# ANALOG_IO.net
KiCad netlist of a schematic drawn in Altium Designer
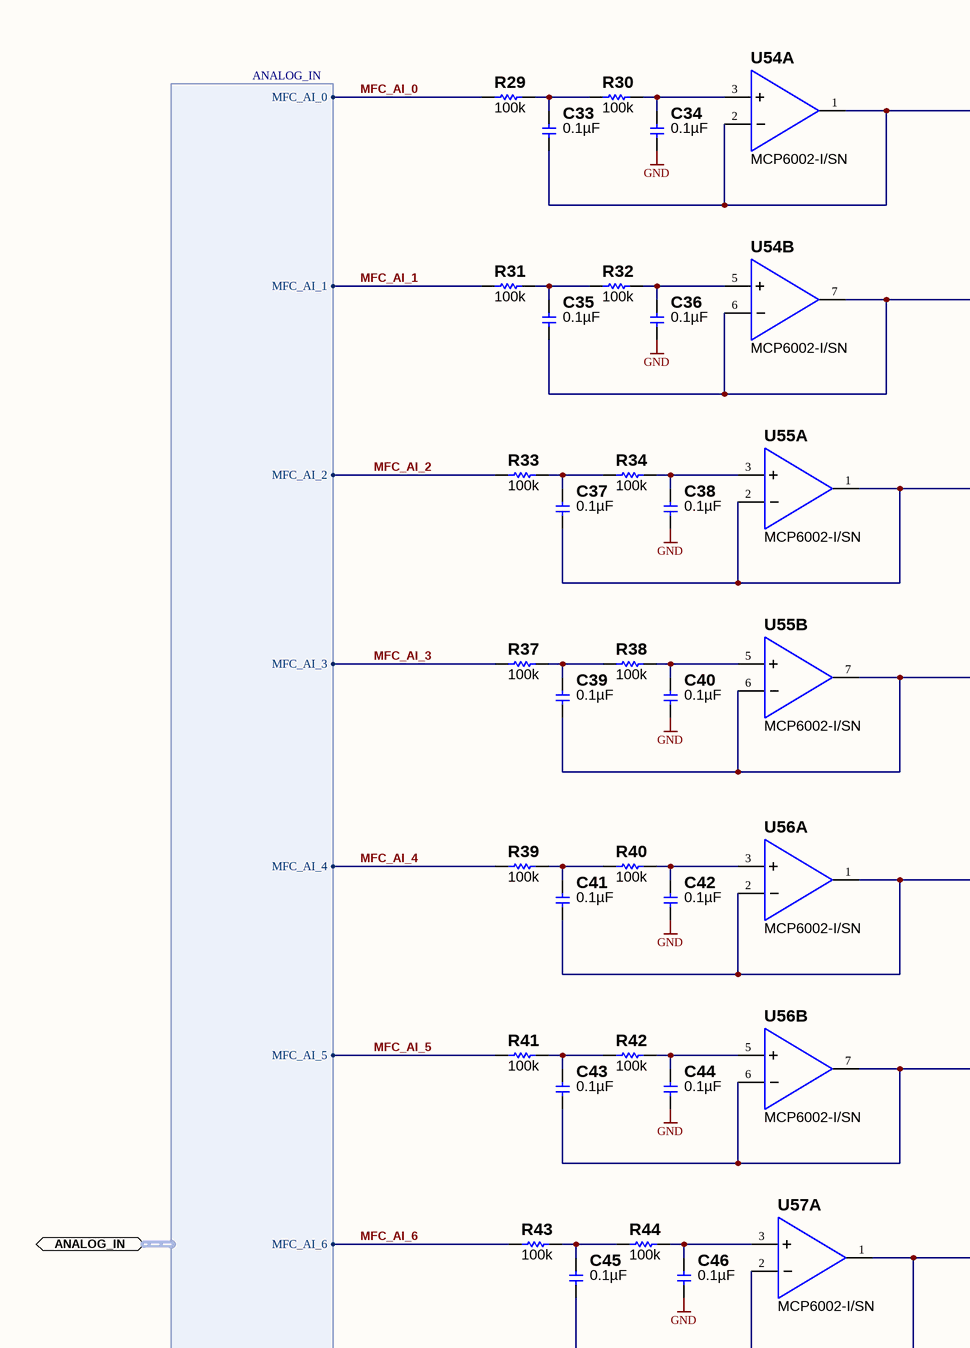
[diagram p0: ANALOG_IO.SchDoc, top left]
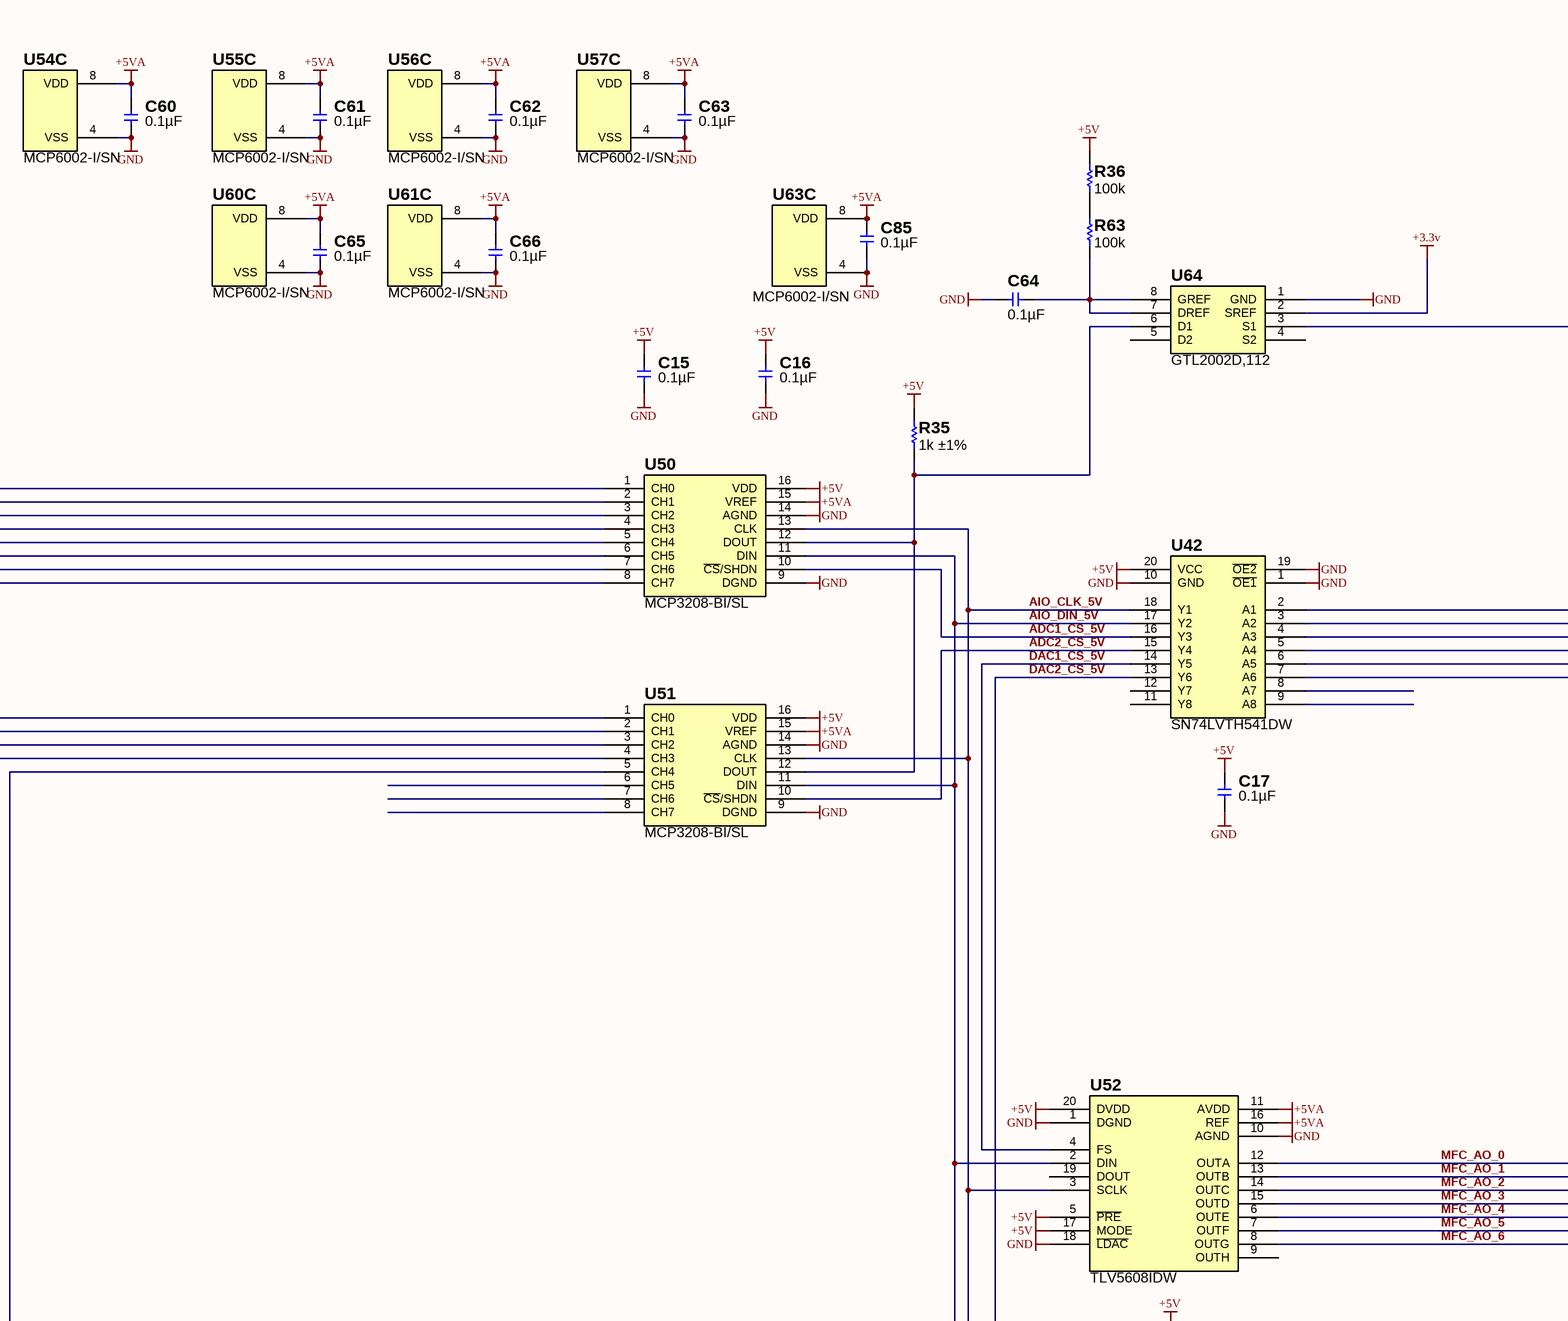
[diagram p1: ANALOG_IO.SchDoc, top middle]
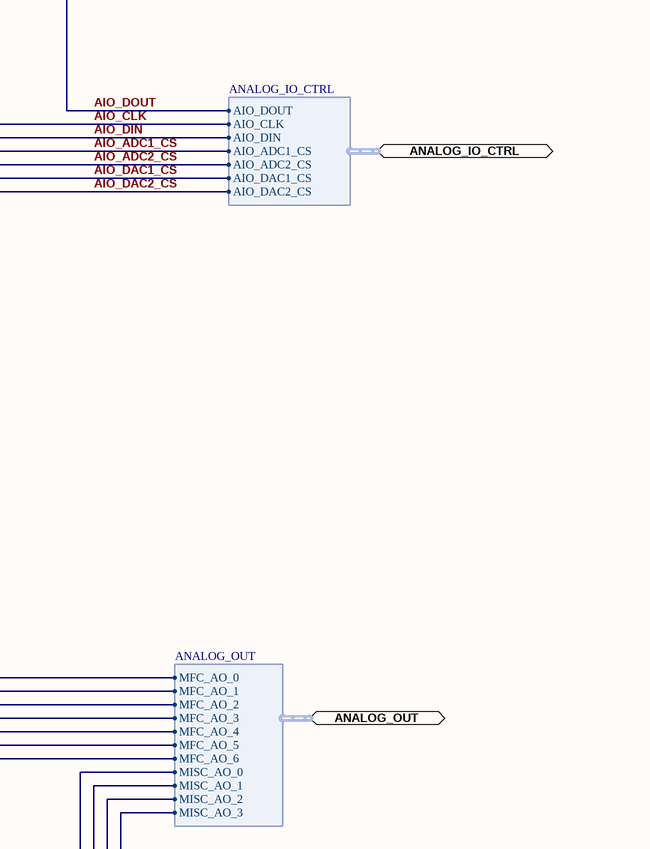
[diagram p2: ANALOG_IO.SchDoc, top right]
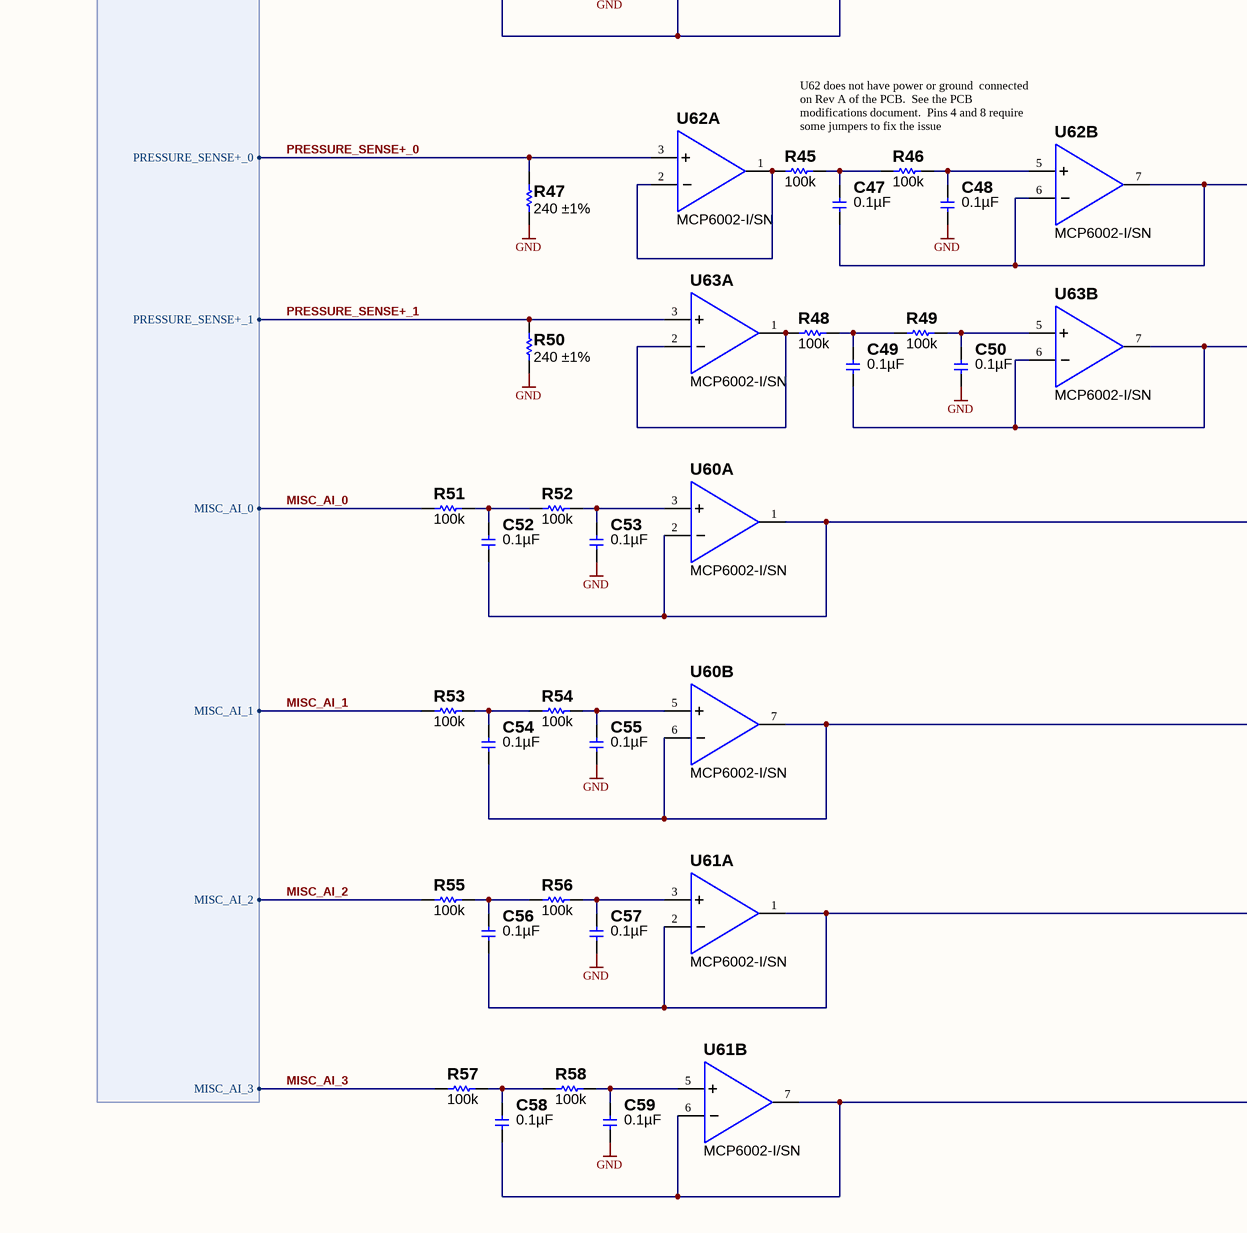
[diagram p3: ANALOG_IO.SchDoc, bottom left]
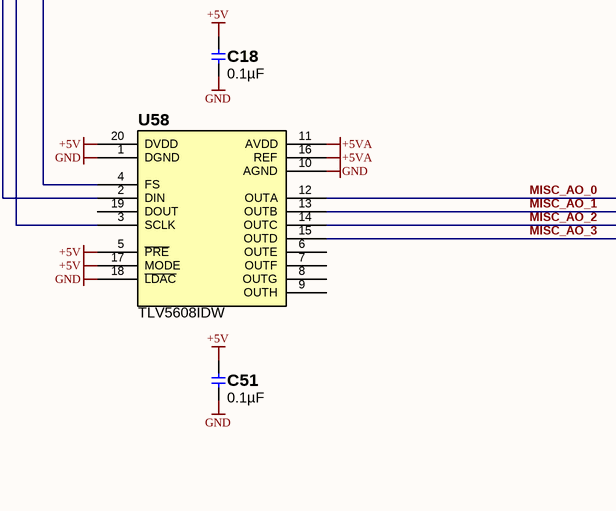
[diagram p4: ANALOG_IO.SchDoc, bottom middle]
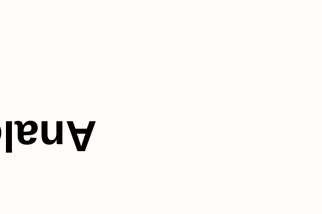
[diagram p5: ANALOG_IO.SchDoc, bottom right]

(export (version "E")
  (design (tool "Eeschema 10.0.6"))
  (components
    (comp (ref "C15")
      (value "0.1µF")
      (footprint "C0805_LD")
      (description "CAP CER 0.1UF 50V 10% X7R 0805")
      (fields
        (field (name "MANUFACTURER PART NUMBER") "GRM21BR71H104KA01L")
        (field (name "MANUFACTURER") "Murata Electronics North America")
      )
      (libsource (lib "Capacitors") (part "C_2P_NP"))
    )
    (comp (ref "C16")
      (value "0.1µF")
      (footprint "C0805_LD")
      (description "CAP CER 0.1UF 50V 10% X7R 0805")
      (fields
        (field (name "MANUFACTURER PART NUMBER") "GRM21BR71H104KA01L")
        (field (name "MANUFACTURER") "Murata Electronics North America")
      )
      (libsource (lib "Capacitors") (part "C_2P_NP"))
    )
    (comp (ref "C17")
      (value "0.1µF")
      (footprint "C0805_LD")
      (description "CAP CER 0.1UF 50V 10% X7R 0805")
      (fields
        (field (name "MANUFACTURER PART NUMBER") "GRM21BR71H104KA01L")
        (field (name "MANUFACTURER") "Murata Electronics North America")
      )
      (libsource (lib "Capacitors") (part "C_2P_NP"))
    )
    (comp (ref "C18")
      (value "0.1µF")
      (footprint "C0805_LD")
      (description "CAP CER 0.1UF 50V 10% X7R 0805")
      (fields
        (field (name "MANUFACTURER PART NUMBER") "GRM21BR71H104KA01L")
        (field (name "MANUFACTURER") "Murata Electronics North America")
      )
      (libsource (lib "Capacitors") (part "C_2P_NP"))
    )
    (comp (ref "C33")
      (value "0.1µF")
      (footprint "C0805_LD")
      (description "CAP CER 0.1UF 50V 10% X7R 0805")
      (fields
        (field (name "MANUFACTURER PART NUMBER") "GRM21BR71H104KA01L")
        (field (name "MANUFACTURER") "Murata Electronics North America")
      )
      (libsource (lib "Capacitors") (part "C_2P_NP"))
    )
    (comp (ref "C34")
      (value "0.1µF")
      (footprint "C0805_LD")
      (description "CAP CER 0.1UF 50V 10% X7R 0805")
      (fields
        (field (name "MANUFACTURER PART NUMBER") "GRM21BR71H104KA01L")
        (field (name "MANUFACTURER") "Murata Electronics North America")
      )
      (libsource (lib "Capacitors") (part "C_2P_NP"))
    )
    (comp (ref "C35")
      (value "0.1µF")
      (footprint "C0805_LD")
      (description "CAP CER 0.1UF 50V 10% X7R 0805")
      (fields
        (field (name "MANUFACTURER PART NUMBER") "GRM21BR71H104KA01L")
        (field (name "MANUFACTURER") "Murata Electronics North America")
      )
      (libsource (lib "Capacitors") (part "C_2P_NP"))
    )
    (comp (ref "C36")
      (value "0.1µF")
      (footprint "C0805_LD")
      (description "CAP CER 0.1UF 50V 10% X7R 0805")
      (fields
        (field (name "MANUFACTURER PART NUMBER") "GRM21BR71H104KA01L")
        (field (name "MANUFACTURER") "Murata Electronics North America")
      )
      (libsource (lib "Capacitors") (part "C_2P_NP"))
    )
    (comp (ref "C37")
      (value "0.1µF")
      (footprint "C0805_LD")
      (description "CAP CER 0.1UF 50V 10% X7R 0805")
      (fields
        (field (name "MANUFACTURER PART NUMBER") "GRM21BR71H104KA01L")
        (field (name "MANUFACTURER") "Murata Electronics North America")
      )
      (libsource (lib "Capacitors") (part "C_2P_NP"))
    )
    (comp (ref "C38")
      (value "0.1µF")
      (footprint "C0805_LD")
      (description "CAP CER 0.1UF 50V 10% X7R 0805")
      (fields
        (field (name "MANUFACTURER PART NUMBER") "GRM21BR71H104KA01L")
        (field (name "MANUFACTURER") "Murata Electronics North America")
      )
      (libsource (lib "Capacitors") (part "C_2P_NP"))
    )
    (comp (ref "C39")
      (value "0.1µF")
      (footprint "C0805_LD")
      (description "CAP CER 0.1UF 50V 10% X7R 0805")
      (fields
        (field (name "MANUFACTURER PART NUMBER") "GRM21BR71H104KA01L")
        (field (name "MANUFACTURER") "Murata Electronics North America")
      )
      (libsource (lib "Capacitors") (part "C_2P_NP"))
    )
    (comp (ref "C40")
      (value "0.1µF")
      (footprint "C0805_LD")
      (description "CAP CER 0.1UF 50V 10% X7R 0805")
      (fields
        (field (name "MANUFACTURER PART NUMBER") "GRM21BR71H104KA01L")
        (field (name "MANUFACTURER") "Murata Electronics North America")
      )
      (libsource (lib "Capacitors") (part "C_2P_NP"))
    )
    (comp (ref "C41")
      (value "0.1µF")
      (footprint "C0805_LD")
      (description "CAP CER 0.1UF 50V 10% X7R 0805")
      (fields
        (field (name "MANUFACTURER PART NUMBER") "GRM21BR71H104KA01L")
        (field (name "MANUFACTURER") "Murata Electronics North America")
      )
      (libsource (lib "Capacitors") (part "C_2P_NP"))
    )
    (comp (ref "C42")
      (value "0.1µF")
      (footprint "C0805_LD")
      (description "CAP CER 0.1UF 50V 10% X7R 0805")
      (fields
        (field (name "MANUFACTURER PART NUMBER") "GRM21BR71H104KA01L")
        (field (name "MANUFACTURER") "Murata Electronics North America")
      )
      (libsource (lib "Capacitors") (part "C_2P_NP"))
    )
    (comp (ref "C43")
      (value "0.1µF")
      (footprint "C0805_LD")
      (description "CAP CER 0.1UF 50V 10% X7R 0805")
      (fields
        (field (name "MANUFACTURER PART NUMBER") "GRM21BR71H104KA01L")
        (field (name "MANUFACTURER") "Murata Electronics North America")
      )
      (libsource (lib "Capacitors") (part "C_2P_NP"))
    )
    (comp (ref "C44")
      (value "0.1µF")
      (footprint "C0805_LD")
      (description "CAP CER 0.1UF 50V 10% X7R 0805")
      (fields
        (field (name "MANUFACTURER PART NUMBER") "GRM21BR71H104KA01L")
        (field (name "MANUFACTURER") "Murata Electronics North America")
      )
      (libsource (lib "Capacitors") (part "C_2P_NP"))
    )
    (comp (ref "C45")
      (value "0.1µF")
      (footprint "C0805_LD")
      (description "CAP CER 0.1UF 50V 10% X7R 0805")
      (fields
        (field (name "MANUFACTURER PART NUMBER") "GRM21BR71H104KA01L")
        (field (name "MANUFACTURER") "Murata Electronics North America")
      )
      (libsource (lib "Capacitors") (part "C_2P_NP"))
    )
    (comp (ref "C46")
      (value "0.1µF")
      (footprint "C0805_LD")
      (description "CAP CER 0.1UF 50V 10% X7R 0805")
      (fields
        (field (name "MANUFACTURER PART NUMBER") "GRM21BR71H104KA01L")
        (field (name "MANUFACTURER") "Murata Electronics North America")
      )
      (libsource (lib "Capacitors") (part "C_2P_NP"))
    )
    (comp (ref "C47")
      (value "0.1µF")
      (footprint "C0805_LD")
      (description "CAP CER 0.1UF 50V 10% X7R 0805")
      (fields
        (field (name "MANUFACTURER PART NUMBER") "GRM21BR71H104KA01L")
        (field (name "MANUFACTURER") "Murata Electronics North America")
      )
      (libsource (lib "Capacitors") (part "C_2P_NP"))
    )
    (comp (ref "C48")
      (value "0.1µF")
      (footprint "C0805_LD")
      (description "CAP CER 0.1UF 50V 10% X7R 0805")
      (fields
        (field (name "MANUFACTURER PART NUMBER") "GRM21BR71H104KA01L")
        (field (name "MANUFACTURER") "Murata Electronics North America")
      )
      (libsource (lib "Capacitors") (part "C_2P_NP"))
    )
    (comp (ref "C49")
      (value "0.1µF")
      (footprint "C0805_LD")
      (description "CAP CER 0.1UF 50V 10% X7R 0805")
      (fields
        (field (name "MANUFACTURER PART NUMBER") "GRM21BR71H104KA01L")
        (field (name "MANUFACTURER") "Murata Electronics North America")
      )
      (libsource (lib "Capacitors") (part "C_2P_NP"))
    )
    (comp (ref "C50")
      (value "0.1µF")
      (footprint "C0805_LD")
      (description "CAP CER 0.1UF 50V 10% X7R 0805")
      (fields
        (field (name "MANUFACTURER PART NUMBER") "GRM21BR71H104KA01L")
        (field (name "MANUFACTURER") "Murata Electronics North America")
      )
      (libsource (lib "Capacitors") (part "C_2P_NP"))
    )
    (comp (ref "C51")
      (value "0.1µF")
      (footprint "C0805_LD")
      (description "CAP CER 0.1UF 50V 10% X7R 0805")
      (fields
        (field (name "MANUFACTURER PART NUMBER") "GRM21BR71H104KA01L")
        (field (name "MANUFACTURER") "Murata Electronics North America")
      )
      (libsource (lib "Capacitors") (part "C_2P_NP"))
    )
    (comp (ref "C52")
      (value "0.1µF")
      (footprint "C0805_LD")
      (description "CAP CER 0.1UF 50V 10% X7R 0805")
      (fields
        (field (name "MANUFACTURER PART NUMBER") "GRM21BR71H104KA01L")
        (field (name "MANUFACTURER") "Murata Electronics North America")
      )
      (libsource (lib "Capacitors") (part "C_2P_NP"))
    )
    (comp (ref "C53")
      (value "0.1µF")
      (footprint "C0805_LD")
      (description "CAP CER 0.1UF 50V 10% X7R 0805")
      (fields
        (field (name "MANUFACTURER PART NUMBER") "GRM21BR71H104KA01L")
        (field (name "MANUFACTURER") "Murata Electronics North America")
      )
      (libsource (lib "Capacitors") (part "C_2P_NP"))
    )
    (comp (ref "C54")
      (value "0.1µF")
      (footprint "C0805_LD")
      (description "CAP CER 0.1UF 50V 10% X7R 0805")
      (fields
        (field (name "MANUFACTURER PART NUMBER") "GRM21BR71H104KA01L")
        (field (name "MANUFACTURER") "Murata Electronics North America")
      )
      (libsource (lib "Capacitors") (part "C_2P_NP"))
    )
    (comp (ref "C55")
      (value "0.1µF")
      (footprint "C0805_LD")
      (description "CAP CER 0.1UF 50V 10% X7R 0805")
      (fields
        (field (name "MANUFACTURER PART NUMBER") "GRM21BR71H104KA01L")
        (field (name "MANUFACTURER") "Murata Electronics North America")
      )
      (libsource (lib "Capacitors") (part "C_2P_NP"))
    )
    (comp (ref "C56")
      (value "0.1µF")
      (footprint "C0805_LD")
      (description "CAP CER 0.1UF 50V 10% X7R 0805")
      (fields
        (field (name "MANUFACTURER PART NUMBER") "GRM21BR71H104KA01L")
        (field (name "MANUFACTURER") "Murata Electronics North America")
      )
      (libsource (lib "Capacitors") (part "C_2P_NP"))
    )
    (comp (ref "C57")
      (value "0.1µF")
      (footprint "C0805_LD")
      (description "CAP CER 0.1UF 50V 10% X7R 0805")
      (fields
        (field (name "MANUFACTURER PART NUMBER") "GRM21BR71H104KA01L")
        (field (name "MANUFACTURER") "Murata Electronics North America")
      )
      (libsource (lib "Capacitors") (part "C_2P_NP"))
    )
    (comp (ref "C58")
      (value "0.1µF")
      (footprint "C0805_LD")
      (description "CAP CER 0.1UF 50V 10% X7R 0805")
      (fields
        (field (name "MANUFACTURER PART NUMBER") "GRM21BR71H104KA01L")
        (field (name "MANUFACTURER") "Murata Electronics North America")
      )
      (libsource (lib "Capacitors") (part "C_2P_NP"))
    )
    (comp (ref "C59")
      (value "0.1µF")
      (footprint "C0805_LD")
      (description "CAP CER 0.1UF 50V 10% X7R 0805")
      (fields
        (field (name "MANUFACTURER PART NUMBER") "GRM21BR71H104KA01L")
        (field (name "MANUFACTURER") "Murata Electronics North America")
      )
      (libsource (lib "Capacitors") (part "C_2P_NP"))
    )
    (comp (ref "C60")
      (value "0.1µF")
      (footprint "C0805_LD")
      (description "CAP CER 0.1UF 50V 10% X7R 0805")
      (fields
        (field (name "MANUFACTURER PART NUMBER") "GRM21BR71H104KA01L")
        (field (name "MANUFACTURER") "Murata Electronics North America")
      )
      (libsource (lib "Capacitors") (part "C_2P_NP"))
    )
    (comp (ref "C61")
      (value "0.1µF")
      (footprint "C0805_LD")
      (description "CAP CER 0.1UF 50V 10% X7R 0805")
      (fields
        (field (name "MANUFACTURER PART NUMBER") "GRM21BR71H104KA01L")
        (field (name "MANUFACTURER") "Murata Electronics North America")
      )
      (libsource (lib "Capacitors") (part "C_2P_NP"))
    )
    (comp (ref "C62")
      (value "0.1µF")
      (footprint "C0805_LD")
      (description "CAP CER 0.1UF 50V 10% X7R 0805")
      (fields
        (field (name "MANUFACTURER PART NUMBER") "GRM21BR71H104KA01L")
        (field (name "MANUFACTURER") "Murata Electronics North America")
      )
      (libsource (lib "Capacitors") (part "C_2P_NP"))
    )
    (comp (ref "C63")
      (value "0.1µF")
      (footprint "C0805_LD")
      (description "CAP CER 0.1UF 50V 10% X7R 0805")
      (fields
        (field (name "MANUFACTURER PART NUMBER") "GRM21BR71H104KA01L")
        (field (name "MANUFACTURER") "Murata Electronics North America")
      )
      (libsource (lib "Capacitors") (part "C_2P_NP"))
    )
    (comp (ref "C64")
      (value "0.1µF")
      (footprint "C0805_LD")
      (description "CAP CER 0.1UF 50V 10% X7R 0805")
      (fields
        (field (name "MANUFACTURER PART NUMBER") "GRM21BR71H104KA01L")
        (field (name "MANUFACTURER") "Murata Electronics North America")
      )
      (libsource (lib "Capacitors") (part "C_2P_NP"))
    )
    (comp (ref "C65")
      (value "0.1µF")
      (footprint "C0805_LD")
      (description "CAP CER 0.1UF 50V 10% X7R 0805")
      (fields
        (field (name "MANUFACTURER PART NUMBER") "GRM21BR71H104KA01L")
        (field (name "MANUFACTURER") "Murata Electronics North America")
      )
      (libsource (lib "Capacitors") (part "C_2P_NP"))
    )
    (comp (ref "C66")
      (value "0.1µF")
      (footprint "C0805_LD")
      (description "CAP CER 0.1UF 50V 10% X7R 0805")
      (fields
        (field (name "MANUFACTURER PART NUMBER") "GRM21BR71H104KA01L")
        (field (name "MANUFACTURER") "Murata Electronics North America")
      )
      (libsource (lib "Capacitors") (part "C_2P_NP"))
    )
    (comp (ref "C85")
      (value "0.1µF")
      (footprint "C0805_LD")
      (description "CAP CER 0.1UF 50V 10% X7R 0805")
      (fields
        (field (name "MANUFACTURER PART NUMBER") "GRM21BR71H104KA01L")
        (field (name "MANUFACTURER") "Murata Electronics North America")
      )
      (libsource (lib "Capacitors") (part "C_2P_NP"))
    )
    (comp (ref "R29")
      (value "100k")
      (footprint "R0805_LD")
      (description "RES 100K OHM 1/8W 1% 0805 SMD")
      (fields
        (field (name "MANUFACTURER PART NUMBER") "ERJ-6ENF1003V")
        (field (name "MANUFACTURER") "Panasonic Electronic Components")
      )
      (libsource (lib "Resistors") (part "R_2P"))
    )
    (comp (ref "R30")
      (value "100k")
      (footprint "R0805_LD")
      (description "RES 100K OHM 1/8W 1% 0805 SMD")
      (fields
        (field (name "MANUFACTURER PART NUMBER") "ERJ-6ENF1003V")
        (field (name "MANUFACTURER") "Panasonic Electronic Components")
      )
      (libsource (lib "Resistors") (part "R_2P"))
    )
    (comp (ref "R31")
      (value "100k")
      (footprint "R0805_LD")
      (description "RES 100K OHM 1/8W 1% 0805 SMD")
      (fields
        (field (name "MANUFACTURER PART NUMBER") "ERJ-6ENF1003V")
        (field (name "MANUFACTURER") "Panasonic Electronic Components")
      )
      (libsource (lib "Resistors") (part "R_2P"))
    )
    (comp (ref "R32")
      (value "100k")
      (footprint "R0805_LD")
      (description "RES 100K OHM 1/8W 1% 0805 SMD")
      (fields
        (field (name "MANUFACTURER PART NUMBER") "ERJ-6ENF1003V")
        (field (name "MANUFACTURER") "Panasonic Electronic Components")
      )
      (libsource (lib "Resistors") (part "R_2P"))
    )
    (comp (ref "R33")
      (value "100k")
      (footprint "R0805_LD")
      (description "RES 100K OHM 1/8W 1% 0805 SMD")
      (fields
        (field (name "MANUFACTURER PART NUMBER") "ERJ-6ENF1003V")
        (field (name "MANUFACTURER") "Panasonic Electronic Components")
      )
      (libsource (lib "Resistors") (part "R_2P"))
    )
    (comp (ref "R34")
      (value "100k")
      (footprint "R0805_LD")
      (description "RES 100K OHM 1/8W 1% 0805 SMD")
      (fields
        (field (name "MANUFACTURER PART NUMBER") "ERJ-6ENF1003V")
        (field (name "MANUFACTURER") "Panasonic Electronic Components")
      )
      (libsource (lib "Resistors") (part "R_2P"))
    )
    (comp (ref "R35")
      (value "1k ±1%")
      (footprint "R0805_LD")
      (description "RES 1K OHM 1/8W 1% 0805 SMD")
      (fields
        (field (name "MANUFACTURER PART NUMBER") "ERJ-6ENF1001V")
        (field (name "MANUFACTURER") "Panasonic Electronic Components")
      )
      (libsource (lib "Resistors") (part "R_2P"))
    )
    (comp (ref "R36")
      (value "100k")
      (footprint "R0805_LD")
      (description "RES 100K OHM 1/8W 1% 0805 SMD")
      (fields
        (field (name "MANUFACTURER PART NUMBER") "ERJ-6ENF1003V")
        (field (name "MANUFACTURER") "Panasonic Electronic Components")
      )
      (libsource (lib "Resistors") (part "R_2P"))
    )
    (comp (ref "R37")
      (value "100k")
      (footprint "R0805_LD")
      (description "RES 100K OHM 1/8W 1% 0805 SMD")
      (fields
        (field (name "MANUFACTURER PART NUMBER") "ERJ-6ENF1003V")
        (field (name "MANUFACTURER") "Panasonic Electronic Components")
      )
      (libsource (lib "Resistors") (part "R_2P"))
    )
    (comp (ref "R38")
      (value "100k")
      (footprint "R0805_LD")
      (description "RES 100K OHM 1/8W 1% 0805 SMD")
      (fields
        (field (name "MANUFACTURER PART NUMBER") "ERJ-6ENF1003V")
        (field (name "MANUFACTURER") "Panasonic Electronic Components")
      )
      (libsource (lib "Resistors") (part "R_2P"))
    )
    (comp (ref "R39")
      (value "100k")
      (footprint "R0805_LD")
      (description "RES 100K OHM 1/8W 1% 0805 SMD")
      (fields
        (field (name "MANUFACTURER PART NUMBER") "ERJ-6ENF1003V")
        (field (name "MANUFACTURER") "Panasonic Electronic Components")
      )
      (libsource (lib "Resistors") (part "R_2P"))
    )
    (comp (ref "R40")
      (value "100k")
      (footprint "R0805_LD")
      (description "RES 100K OHM 1/8W 1% 0805 SMD")
      (fields
        (field (name "MANUFACTURER PART NUMBER") "ERJ-6ENF1003V")
        (field (name "MANUFACTURER") "Panasonic Electronic Components")
      )
      (libsource (lib "Resistors") (part "R_2P"))
    )
    (comp (ref "R41")
      (value "100k")
      (footprint "R0805_LD")
      (description "RES 100K OHM 1/8W 1% 0805 SMD")
      (fields
        (field (name "MANUFACTURER PART NUMBER") "ERJ-6ENF1003V")
        (field (name "MANUFACTURER") "Panasonic Electronic Components")
      )
      (libsource (lib "Resistors") (part "R_2P"))
    )
    (comp (ref "R42")
      (value "100k")
      (footprint "R0805_LD")
      (description "RES 100K OHM 1/8W 1% 0805 SMD")
      (fields
        (field (name "MANUFACTURER PART NUMBER") "ERJ-6ENF1003V")
        (field (name "MANUFACTURER") "Panasonic Electronic Components")
      )
      (libsource (lib "Resistors") (part "R_2P"))
    )
    (comp (ref "R43")
      (value "100k")
      (footprint "R0805_LD")
      (description "RES 100K OHM 1/8W 1% 0805 SMD")
      (fields
        (field (name "MANUFACTURER PART NUMBER") "ERJ-6ENF1003V")
        (field (name "MANUFACTURER") "Panasonic Electronic Components")
      )
      (libsource (lib "Resistors") (part "R_2P"))
    )
    (comp (ref "R44")
      (value "100k")
      (footprint "R0805_LD")
      (description "RES 100K OHM 1/8W 1% 0805 SMD")
      (fields
        (field (name "MANUFACTURER PART NUMBER") "ERJ-6ENF1003V")
        (field (name "MANUFACTURER") "Panasonic Electronic Components")
      )
      (libsource (lib "Resistors") (part "R_2P"))
    )
    (comp (ref "R45")
      (value "100k")
      (footprint "R0805_LD")
      (description "RES 100K OHM 1/8W 1% 0805 SMD")
      (fields
        (field (name "MANUFACTURER PART NUMBER") "ERJ-6ENF1003V")
        (field (name "MANUFACTURER") "Panasonic Electronic Components")
      )
      (libsource (lib "Resistors") (part "R_2P"))
    )
    (comp (ref "R46")
      (value "100k")
      (footprint "R0805_LD")
      (description "RES 100K OHM 1/8W 1% 0805 SMD")
      (fields
        (field (name "MANUFACTURER PART NUMBER") "ERJ-6ENF1003V")
        (field (name "MANUFACTURER") "Panasonic Electronic Components")
      )
      (libsource (lib "Resistors") (part "R_2P"))
    )
    (comp (ref "R47")
      (value "240 ±1%")
      (footprint "R0805_LD")
      (description "RES 240 OHM 1/8W 1% 0805 SMD")
      (fields
        (field (name "MANUFACTURER PART NUMBER") "ERJ-6ENF2400V")
        (field (name "MANUFACTURER") "Panasonic Electronic Components")
      )
      (libsource (lib "Resistors") (part "R_2P"))
    )
    (comp (ref "R48")
      (value "100k")
      (footprint "R0805_LD")
      (description "RES 100K OHM 1/8W 1% 0805 SMD")
      (fields
        (field (name "MANUFACTURER PART NUMBER") "ERJ-6ENF1003V")
        (field (name "MANUFACTURER") "Panasonic Electronic Components")
      )
      (libsource (lib "Resistors") (part "R_2P"))
    )
    (comp (ref "R49")
      (value "100k")
      (footprint "R0805_LD")
      (description "RES 100K OHM 1/8W 1% 0805 SMD")
      (fields
        (field (name "MANUFACTURER PART NUMBER") "ERJ-6ENF1003V")
        (field (name "MANUFACTURER") "Panasonic Electronic Components")
      )
      (libsource (lib "Resistors") (part "R_2P"))
    )
    (comp (ref "R50")
      (value "240 ±1%")
      (footprint "R0805_LD")
      (description "RES 240 OHM 1/8W 1% 0805 SMD")
      (fields
        (field (name "MANUFACTURER PART NUMBER") "ERJ-6ENF2400V")
        (field (name "MANUFACTURER") "Panasonic Electronic Components")
      )
      (libsource (lib "Resistors") (part "R_2P"))
    )
    (comp (ref "R51")
      (value "100k")
      (footprint "R0805_LD")
      (description "RES 100K OHM 1/8W 1% 0805 SMD")
      (fields
        (field (name "MANUFACTURER PART NUMBER") "ERJ-6ENF1003V")
        (field (name "MANUFACTURER") "Panasonic Electronic Components")
      )
      (libsource (lib "Resistors") (part "R_2P"))
    )
    (comp (ref "R52")
      (value "100k")
      (footprint "R0805_LD")
      (description "RES 100K OHM 1/8W 1% 0805 SMD")
      (fields
        (field (name "MANUFACTURER PART NUMBER") "ERJ-6ENF1003V")
        (field (name "MANUFACTURER") "Panasonic Electronic Components")
      )
      (libsource (lib "Resistors") (part "R_2P"))
    )
    (comp (ref "R53")
      (value "100k")
      (footprint "R0805_LD")
      (description "RES 100K OHM 1/8W 1% 0805 SMD")
      (fields
        (field (name "MANUFACTURER PART NUMBER") "ERJ-6ENF1003V")
        (field (name "MANUFACTURER") "Panasonic Electronic Components")
      )
      (libsource (lib "Resistors") (part "R_2P"))
    )
    (comp (ref "R54")
      (value "100k")
      (footprint "R0805_LD")
      (description "RES 100K OHM 1/8W 1% 0805 SMD")
      (fields
        (field (name "MANUFACTURER PART NUMBER") "ERJ-6ENF1003V")
        (field (name "MANUFACTURER") "Panasonic Electronic Components")
      )
      (libsource (lib "Resistors") (part "R_2P"))
    )
    (comp (ref "R55")
      (value "100k")
      (footprint "R0805_LD")
      (description "RES 100K OHM 1/8W 1% 0805 SMD")
      (fields
        (field (name "MANUFACTURER PART NUMBER") "ERJ-6ENF1003V")
        (field (name "MANUFACTURER") "Panasonic Electronic Components")
      )
      (libsource (lib "Resistors") (part "R_2P"))
    )
    (comp (ref "R56")
      (value "100k")
      (footprint "R0805_LD")
      (description "RES 100K OHM 1/8W 1% 0805 SMD")
      (fields
        (field (name "MANUFACTURER PART NUMBER") "ERJ-6ENF1003V")
        (field (name "MANUFACTURER") "Panasonic Electronic Components")
      )
      (libsource (lib "Resistors") (part "R_2P"))
    )
    (comp (ref "R57")
      (value "100k")
      (footprint "R0805_LD")
      (description "RES 100K OHM 1/8W 1% 0805 SMD")
      (fields
        (field (name "MANUFACTURER PART NUMBER") "ERJ-6ENF1003V")
        (field (name "MANUFACTURER") "Panasonic Electronic Components")
      )
      (libsource (lib "Resistors") (part "R_2P"))
    )
    (comp (ref "R58")
      (value "100k")
      (footprint "R0805_LD")
      (description "RES 100K OHM 1/8W 1% 0805 SMD")
      (fields
        (field (name "MANUFACTURER PART NUMBER") "ERJ-6ENF1003V")
        (field (name "MANUFACTURER") "Panasonic Electronic Components")
      )
      (libsource (lib "Resistors") (part "R_2P"))
    )
    (comp (ref "R63")
      (value "100k")
      (footprint "R0805_LD")
      (description "RES 100K OHM 1/8W 1% 0805 SMD")
      (fields
        (field (name "MANUFACTURER PART NUMBER") "ERJ-6ENF1003V")
        (field (name "MANUFACTURER") "Panasonic Electronic Components")
      )
      (libsource (lib "Resistors") (part "R_2P"))
    )
    (comp (ref "U42")
      (value "SN74LVTH541DW")
      (footprint "SOIC127P1030X265-20L")
      (description "IC BUFF/DVR TRI-ST 8BIT 20SOIC")
      (fields (field (name "MANUFACTURER") "Texas Instruments"))
      (libsource (lib "eIC") (part "SN74LVTH541DW"))
    )
    (comp (ref "U50")
      (value "MCP3208-BI/SL")
      (footprint "SOIC127P600X145-16L")
      (description "IC ADC 12BIT 2.7V 8CH SPI 16SOIC")
      (fields (field (name "MANUFACTURER") "Microchip Technology"))
      (libsource (lib "eIC") (part "MCP3208-BI/SL"))
    )
    (comp (ref "U51")
      (value "MCP3208-BI/SL")
      (footprint "SOIC127P600X145-16L")
      (description "IC ADC 12BIT 2.7V 8CH SPI 16SOIC")
      (fields (field (name "MANUFACTURER") "Microchip Technology"))
      (libsource (lib "eIC") (part "MCP3208-BI/SL"))
    )
    (comp (ref "U52")
      (value "TLV5608IDW")
      (footprint "SOIC127P1030X265-20L")
      (description "IC 8 CHANNEL DAC S/O 20-SOIC")
      (fields (field (name "MANUFACTURER") "Texas Instruments"))
      (libsource (lib "eIC") (part "TLV5608IDW"))
    )
    (comp (ref "U54")
      (value "MCP6002-I/SN")
      (footprint "SOIC 8")
      (description "IC OPAMP 1.8V 1MHZ DUAL 8-SOIC")
      (fields (field (name "MANUFACTURER") "Microchip Technology"))
      (libsource (lib "eIC") (part "MCP6002-I/SN"))
    )
    (comp (ref "U55")
      (value "MCP6002-I/SN")
      (footprint "SOIC 8")
      (description "IC OPAMP 1.8V 1MHZ DUAL 8-SOIC")
      (fields (field (name "MANUFACTURER") "Microchip Technology"))
      (libsource (lib "eIC") (part "MCP6002-I/SN"))
    )
    (comp (ref "U56")
      (value "MCP6002-I/SN")
      (footprint "SOIC 8")
      (description "IC OPAMP 1.8V 1MHZ DUAL 8-SOIC")
      (fields (field (name "MANUFACTURER") "Microchip Technology"))
      (libsource (lib "eIC") (part "MCP6002-I/SN"))
    )
    (comp (ref "U57")
      (value "MCP6002-I/SN")
      (footprint "SOIC 8")
      (description "IC OPAMP 1.8V 1MHZ DUAL 8-SOIC")
      (fields (field (name "MANUFACTURER") "Microchip Technology"))
      (libsource (lib "eIC") (part "MCP6002-I/SN"))
    )
    (comp (ref "U58")
      (value "TLV5608IDW")
      (footprint "SOIC127P1030X265-20L")
      (description "IC 8 CHANNEL DAC S/O 20-SOIC")
      (fields (field (name "MANUFACTURER") "Texas Instruments"))
      (libsource (lib "eIC") (part "TLV5608IDW"))
    )
    (comp (ref "U60")
      (value "MCP6002-I/SN")
      (footprint "SOIC 8")
      (description "IC OPAMP 1.8V 1MHZ DUAL 8-SOIC")
      (fields (field (name "MANUFACTURER") "Microchip Technology"))
      (libsource (lib "eIC") (part "MCP6002-I/SN"))
    )
    (comp (ref "U61")
      (value "MCP6002-I/SN")
      (footprint "SOIC 8")
      (description "IC OPAMP 1.8V 1MHZ DUAL 8-SOIC")
      (fields (field (name "MANUFACTURER") "Microchip Technology"))
      (libsource (lib "eIC") (part "MCP6002-I/SN"))
    )
    (comp (ref "U62")
      (value "MCP6002-I/SN")
      (footprint "SOIC 8")
      (description "IC OPAMP 1.8V 1MHZ DUAL 8-SOIC")
      (fields (field (name "MANUFACTURER") "Microchip Technology"))
      (libsource (lib "eIC") (part "MCP6002-I/SN"))
    )
    (comp (ref "U63")
      (value "MCP6002-I/SN")
      (footprint "SOIC 8")
      (description "IC OPAMP 1.8V 1MHZ DUAL 8-SOIC")
      (fields (field (name "MANUFACTURER") "Microchip Technology"))
      (libsource (lib "eIC") (part "MCP6002-I/SN"))
    )
    (comp (ref "U64")
      (value "GTL2002D,112")
      (footprint "SOIC 8")
      (description "IC XLATR 2BIT BI-DIREC 8SOIC")
      (fields (field (name "MANUFACTURER") "NXP Semiconductors"))
      (libsource (lib "eIC") (part "GTL2002D,112"))
    )
  )
  (nets
    (net (code "4") (name "+3.3v") (class "Default")
      (node (ref "U64") (pin "2") (pinfunction "SREF_2") (pintype "passive"))
    )
    (net (code "5") (name "+5V") (class "Default")
      (node (ref "C15") (pin "2") (pinfunction "2_2") (pintype "passive"))
      (node (ref "C16") (pin "2") (pinfunction "2_2") (pintype "passive"))
      (node (ref "C17") (pin "2") (pinfunction "2_2") (pintype "passive"))
      (node (ref "C18") (pin "2") (pinfunction "2_2") (pintype "passive"))
      (node (ref "C51") (pin "2") (pinfunction "2_2") (pintype "passive"))
      (node (ref "R35") (pin "2") (pinfunction "2_2") (pintype "passive"))
      (node (ref "R36") (pin "2") (pinfunction "2_2") (pintype "passive"))
      (node (ref "U42") (pin "20") (pinfunction "VCC_20") (pintype "passive"))
      (node (ref "U50") (pin "16") (pinfunction "VDD_16") (pintype "passive"))
      (node (ref "U51") (pin "16") (pinfunction "VDD_16") (pintype "passive"))
      (node (ref "U52") (pin "17") (pinfunction "MODE_17") (pintype "passive"))
      (node (ref "U52") (pin "20") (pinfunction "DVDD_20") (pintype "passive"))
      (node (ref "U52") (pin "5") (pinfunction "~{PRE}_5") (pintype "passive"))
      (node (ref "U58") (pin "17") (pinfunction "MODE_17") (pintype "passive"))
      (node (ref "U58") (pin "20") (pinfunction "DVDD_20") (pintype "passive"))
      (node (ref "U58") (pin "5") (pinfunction "~{PRE}_5") (pintype "passive"))
    )
    (net (code "6") (name "+5VA") (class "Default")
      (node (ref "C60") (pin "2") (pinfunction "2_2") (pintype "passive"))
      (node (ref "C61") (pin "2") (pinfunction "2_2") (pintype "passive"))
      (node (ref "C62") (pin "2") (pinfunction "2_2") (pintype "passive"))
      (node (ref "C63") (pin "2") (pinfunction "2_2") (pintype "passive"))
      (node (ref "C65") (pin "2") (pinfunction "2_2") (pintype "passive"))
      (node (ref "C66") (pin "2") (pinfunction "2_2") (pintype "passive"))
      (node (ref "C85") (pin "2") (pinfunction "2_2") (pintype "passive"))
      (node (ref "U50") (pin "15") (pinfunction "VREF_15") (pintype "passive"))
      (node (ref "U51") (pin "15") (pinfunction "VREF_15") (pintype "passive"))
      (node (ref "U52") (pin "11") (pinfunction "AVDD_11") (pintype "passive"))
      (node (ref "U52") (pin "16") (pinfunction "REF_16") (pintype "passive"))
      (node (ref "U54") (pin "8") (pinfunction "VDD_8") (pintype "passive"))
      (node (ref "U55") (pin "8") (pinfunction "VDD_8") (pintype "passive"))
      (node (ref "U56") (pin "8") (pinfunction "VDD_8") (pintype "passive"))
      (node (ref "U57") (pin "8") (pinfunction "VDD_8") (pintype "passive"))
      (node (ref "U58") (pin "11") (pinfunction "AVDD_11") (pintype "passive"))
      (node (ref "U58") (pin "16") (pinfunction "REF_16") (pintype "passive"))
      (node (ref "U60") (pin "8") (pinfunction "VDD_8") (pintype "passive"))
      (node (ref "U61") (pin "8") (pinfunction "VDD_8") (pintype "passive"))
      (node (ref "U63") (pin "8") (pinfunction "VDD_8") (pintype "passive"))
    )
    (net (code "7") (name "/ADC1_CS_5V") (class "Default")
      (node (ref "U42") (pin "16") (pinfunction "Y3_16") (pintype "passive"))
      (node (ref "U50") (pin "10") (pinfunction "~{CS}/SHDN_10") (pintype "passive"))
    )
    (net (code "8") (name "/ADC2_CS_5V") (class "Default")
      (node (ref "U42") (pin "15") (pinfunction "Y4_15") (pintype "passive"))
      (node (ref "U51") (pin "10") (pinfunction "~{CS}/SHDN_10") (pintype "passive"))
    )
    (net (code "9") (name "/AIO_ADC1_CS") (class "Default")
      (node (ref "U42") (pin "4") (pinfunction "A3_4") (pintype "passive"))
    )
    (net (code "10") (name "/AIO_ADC2_CS") (class "Default")
      (node (ref "U42") (pin "5") (pinfunction "A4_5") (pintype "passive"))
    )
    (net (code "11") (name "/AIO_CLK") (class "Default")
      (node (ref "U42") (pin "2") (pinfunction "A1_2") (pintype "passive"))
    )
    (net (code "12") (name "/AIO_CLK_5V") (class "Default")
      (node (ref "U42") (pin "18") (pinfunction "Y1_18") (pintype "passive"))
      (node (ref "U50") (pin "13") (pinfunction "CLK_13") (pintype "passive"))
      (node (ref "U51") (pin "13") (pinfunction "CLK_13") (pintype "passive"))
      (node (ref "U52") (pin "3") (pinfunction "SCLK_3") (pintype "passive"))
      (node (ref "U58") (pin "3") (pinfunction "SCLK_3") (pintype "passive"))
    )
    (net (code "13") (name "/AIO_DAC1_CS") (class "Default")
      (node (ref "U42") (pin "6") (pinfunction "A5_6") (pintype "passive"))
    )
    (net (code "14") (name "/AIO_DAC2_CS") (class "Default")
      (node (ref "U42") (pin "7") (pinfunction "A6_7") (pintype "passive"))
    )
    (net (code "15") (name "/AIO_DIN") (class "Default")
      (node (ref "U42") (pin "3") (pinfunction "A2_3") (pintype "passive"))
    )
    (net (code "16") (name "/AIO_DIN_5V") (class "Default")
      (node (ref "U42") (pin "17") (pinfunction "Y2_17") (pintype "passive"))
      (node (ref "U50") (pin "11") (pinfunction "DIN_11") (pintype "passive"))
      (node (ref "U51") (pin "11") (pinfunction "DIN_11") (pintype "passive"))
      (node (ref "U52") (pin "2") (pinfunction "DIN_2") (pintype "passive"))
      (node (ref "U58") (pin "2") (pinfunction "DIN_2") (pintype "passive"))
    )
    (net (code "17") (name "/AIO_DOUT") (class "Default")
      (node (ref "U64") (pin "3") (pinfunction "S1_3") (pintype "passive"))
    )
    (net (code "18") (name "/DAC1_CS_5V") (class "Default")
      (node (ref "U42") (pin "14") (pinfunction "Y5_14") (pintype "passive"))
      (node (ref "U52") (pin "4") (pinfunction "FS_4") (pintype "passive"))
    )
    (net (code "19") (name "/DAC2_CS_5V") (class "Default")
      (node (ref "U42") (pin "13") (pinfunction "Y6_13") (pintype "passive"))
      (node (ref "U58") (pin "4") (pinfunction "FS_4") (pintype "passive"))
    )
    (net (code "20") (name "/MFC_AI_0") (class "Default")
      (node (ref "R29") (pin "1") (pinfunction "1_1") (pintype "passive"))
    )
    (net (code "21") (name "/MFC_AI_1") (class "Default")
      (node (ref "R31") (pin "1") (pinfunction "1_1") (pintype "passive"))
    )
    (net (code "22") (name "/MFC_AI_2") (class "Default")
      (node (ref "R33") (pin "1") (pinfunction "1_1") (pintype "passive"))
    )
    (net (code "23") (name "/MFC_AI_3") (class "Default")
      (node (ref "R37") (pin "1") (pinfunction "1_1") (pintype "passive"))
    )
    (net (code "24") (name "/MFC_AI_4") (class "Default")
      (node (ref "R39") (pin "1") (pinfunction "1_1") (pintype "passive"))
    )
    (net (code "25") (name "/MFC_AI_5") (class "Default")
      (node (ref "R41") (pin "1") (pinfunction "1_1") (pintype "passive"))
    )
    (net (code "26") (name "/MFC_AI_6") (class "Default")
      (node (ref "R43") (pin "1") (pinfunction "1_1") (pintype "passive"))
    )
    (net (code "27") (name "/MFC_AO_0") (class "Default")
      (node (ref "U52") (pin "12") (pinfunction "OUTA_12") (pintype "passive"))
    )
    (net (code "28") (name "/MFC_AO_1") (class "Default")
      (node (ref "U52") (pin "13") (pinfunction "OUTB_13") (pintype "passive"))
    )
    (net (code "29") (name "/MFC_AO_2") (class "Default")
      (node (ref "U52") (pin "14") (pinfunction "OUTC_14") (pintype "passive"))
    )
    (net (code "30") (name "/MFC_AO_3") (class "Default")
      (node (ref "U52") (pin "15") (pinfunction "OUTD_15") (pintype "passive"))
    )
    (net (code "31") (name "/MFC_AO_4") (class "Default")
      (node (ref "U52") (pin "6") (pinfunction "OUTE_6") (pintype "passive"))
    )
    (net (code "32") (name "/MFC_AO_5") (class "Default")
      (node (ref "U52") (pin "7") (pinfunction "OUTF_7") (pintype "passive"))
    )
    (net (code "33") (name "/MFC_AO_6") (class "Default")
      (node (ref "U52") (pin "8") (pinfunction "OUTG_8") (pintype "passive"))
    )
    (net (code "34") (name "/MISC_AI_0") (class "Default")
      (node (ref "R51") (pin "1") (pinfunction "1_1") (pintype "passive"))
    )
    (net (code "35") (name "/MISC_AI_1") (class "Default")
      (node (ref "R53") (pin "1") (pinfunction "1_1") (pintype "passive"))
    )
    (net (code "36") (name "/MISC_AI_2") (class "Default")
      (node (ref "R55") (pin "1") (pinfunction "1_1") (pintype "passive"))
    )
    (net (code "37") (name "/MISC_AI_3") (class "Default")
      (node (ref "R57") (pin "1") (pinfunction "1_1") (pintype "passive"))
    )
    (net (code "38") (name "/MISC_AO_0") (class "Default")
      (node (ref "U58") (pin "12") (pinfunction "OUTA_12") (pintype "passive"))
    )
    (net (code "39") (name "/MISC_AO_1") (class "Default")
      (node (ref "U58") (pin "13") (pinfunction "OUTB_13") (pintype "passive"))
    )
    (net (code "40") (name "/MISC_AO_2") (class "Default")
      (node (ref "U58") (pin "14") (pinfunction "OUTC_14") (pintype "passive"))
    )
    (net (code "41") (name "/MISC_AO_3") (class "Default")
      (node (ref "U58") (pin "15") (pinfunction "OUTD_15") (pintype "passive"))
    )
    (net (code "42") (name "/PRESSURE_SENSE+_0") (class "Default")
      (node (ref "R47") (pin "2") (pinfunction "2_2") (pintype "passive"))
      (node (ref "U62") (pin "3") (pinfunction "+_3") (pintype "passive"))
    )
    (net (code "43") (name "/PRESSURE_SENSE+_1") (class "Default")
      (node (ref "R50") (pin "2") (pinfunction "2_2") (pintype "passive"))
      (node (ref "U63") (pin "3") (pinfunction "+_3") (pintype "passive"))
    )
    (net (code "47") (name "GND") (class "Default")
      (node (ref "C15") (pin "1") (pinfunction "1_1") (pintype "passive"))
      (node (ref "C16") (pin "1") (pinfunction "1_1") (pintype "passive"))
      (node (ref "C17") (pin "1") (pinfunction "1_1") (pintype "passive"))
      (node (ref "C18") (pin "1") (pinfunction "1_1") (pintype "passive"))
      (node (ref "C34") (pin "1") (pinfunction "1_1") (pintype "passive"))
      (node (ref "C36") (pin "1") (pinfunction "1_1") (pintype "passive"))
      (node (ref "C38") (pin "1") (pinfunction "1_1") (pintype "passive"))
      (node (ref "C40") (pin "1") (pinfunction "1_1") (pintype "passive"))
      (node (ref "C42") (pin "1") (pinfunction "1_1") (pintype "passive"))
      (node (ref "C44") (pin "1") (pinfunction "1_1") (pintype "passive"))
      (node (ref "C46") (pin "1") (pinfunction "1_1") (pintype "passive"))
      (node (ref "C48") (pin "1") (pinfunction "1_1") (pintype "passive"))
      (node (ref "C50") (pin "1") (pinfunction "1_1") (pintype "passive"))
      (node (ref "C51") (pin "1") (pinfunction "1_1") (pintype "passive"))
      (node (ref "C53") (pin "1") (pinfunction "1_1") (pintype "passive"))
      (node (ref "C55") (pin "1") (pinfunction "1_1") (pintype "passive"))
      (node (ref "C57") (pin "1") (pinfunction "1_1") (pintype "passive"))
      (node (ref "C59") (pin "1") (pinfunction "1_1") (pintype "passive"))
      (node (ref "C60") (pin "1") (pinfunction "1_1") (pintype "passive"))
      (node (ref "C61") (pin "1") (pinfunction "1_1") (pintype "passive"))
      (node (ref "C62") (pin "1") (pinfunction "1_1") (pintype "passive"))
      (node (ref "C63") (pin "1") (pinfunction "1_1") (pintype "passive"))
      (node (ref "C64") (pin "2") (pinfunction "2_2") (pintype "passive"))
      (node (ref "C65") (pin "1") (pinfunction "1_1") (pintype "passive"))
      (node (ref "C66") (pin "1") (pinfunction "1_1") (pintype "passive"))
      (node (ref "C85") (pin "1") (pinfunction "1_1") (pintype "passive"))
      (node (ref "R47") (pin "1") (pinfunction "1_1") (pintype "passive"))
      (node (ref "R50") (pin "1") (pinfunction "1_1") (pintype "passive"))
      (node (ref "U42") (pin "1") (pinfunction "~{OE1}_1") (pintype "passive"))
      (node (ref "U42") (pin "10") (pinfunction "GND_10") (pintype "passive"))
      (node (ref "U42") (pin "19") (pinfunction "~{OE2}_19") (pintype "passive"))
      (node (ref "U50") (pin "14") (pinfunction "AGND_14") (pintype "passive"))
      (node (ref "U50") (pin "9") (pinfunction "DGND_9") (pintype "passive"))
      (node (ref "U51") (pin "14") (pinfunction "AGND_14") (pintype "passive"))
      (node (ref "U51") (pin "9") (pinfunction "DGND_9") (pintype "passive"))
      (node (ref "U52") (pin "1") (pinfunction "DGND_1") (pintype "passive"))
      (node (ref "U52") (pin "10") (pinfunction "AGND_10") (pintype "passive"))
      (node (ref "U52") (pin "18") (pinfunction "~{LDAC}_18") (pintype "passive"))
      (node (ref "U54") (pin "4") (pinfunction "VSS_4") (pintype "passive"))
      (node (ref "U55") (pin "4") (pinfunction "VSS_4") (pintype "passive"))
      (node (ref "U56") (pin "4") (pinfunction "VSS_4") (pintype "passive"))
      (node (ref "U57") (pin "4") (pinfunction "VSS_4") (pintype "passive"))
      (node (ref "U58") (pin "1") (pinfunction "DGND_1") (pintype "passive"))
      (node (ref "U58") (pin "10") (pinfunction "AGND_10") (pintype "passive"))
      (node (ref "U58") (pin "18") (pinfunction "~{LDAC}_18") (pintype "passive"))
      (node (ref "U60") (pin "4") (pinfunction "VSS_4") (pintype "passive"))
      (node (ref "U61") (pin "4") (pinfunction "VSS_4") (pintype "passive"))
      (node (ref "U63") (pin "4") (pinfunction "VSS_4") (pintype "passive"))
      (node (ref "U64") (pin "1") (pinfunction "GND_1") (pintype "passive"))
    )
    (net (code "48") (name "Net-(C33-Pad2)") (class "Default")
      (node (ref "C33") (pin "2") (pinfunction "2_2") (pintype "passive"))
      (node (ref "R29") (pin "2") (pinfunction "2_2") (pintype "passive"))
      (node (ref "R30") (pin "1") (pinfunction "1_1") (pintype "passive"))
    )
    (net (code "49") (name "Net-(C35-Pad2)") (class "Default")
      (node (ref "C35") (pin "2") (pinfunction "2_2") (pintype "passive"))
      (node (ref "R31") (pin "2") (pinfunction "2_2") (pintype "passive"))
      (node (ref "R32") (pin "1") (pinfunction "1_1") (pintype "passive"))
    )
    (net (code "50") (name "Net-(C37-Pad2)") (class "Default")
      (node (ref "C37") (pin "2") (pinfunction "2_2") (pintype "passive"))
      (node (ref "R33") (pin "2") (pinfunction "2_2") (pintype "passive"))
      (node (ref "R34") (pin "1") (pinfunction "1_1") (pintype "passive"))
    )
    (net (code "51") (name "Net-(C39-Pad2)") (class "Default")
      (node (ref "C39") (pin "2") (pinfunction "2_2") (pintype "passive"))
      (node (ref "R37") (pin "2") (pinfunction "2_2") (pintype "passive"))
      (node (ref "R38") (pin "1") (pinfunction "1_1") (pintype "passive"))
    )
    (net (code "52") (name "Net-(C41-Pad2)") (class "Default")
      (node (ref "C41") (pin "2") (pinfunction "2_2") (pintype "passive"))
      (node (ref "R39") (pin "2") (pinfunction "2_2") (pintype "passive"))
      (node (ref "R40") (pin "1") (pinfunction "1_1") (pintype "passive"))
    )
    (net (code "53") (name "Net-(C43-Pad2)") (class "Default")
      (node (ref "C43") (pin "2") (pinfunction "2_2") (pintype "passive"))
      (node (ref "R41") (pin "2") (pinfunction "2_2") (pintype "passive"))
      (node (ref "R42") (pin "1") (pinfunction "1_1") (pintype "passive"))
    )
    (net (code "54") (name "Net-(C45-Pad2)") (class "Default")
      (node (ref "C45") (pin "2") (pinfunction "2_2") (pintype "passive"))
      (node (ref "R43") (pin "2") (pinfunction "2_2") (pintype "passive"))
      (node (ref "R44") (pin "1") (pinfunction "1_1") (pintype "passive"))
    )
    (net (code "55") (name "Net-(C47-Pad2)") (class "Default")
      (node (ref "C47") (pin "2") (pinfunction "2_2") (pintype "passive"))
      (node (ref "R45") (pin "2") (pinfunction "2_2") (pintype "passive"))
      (node (ref "R46") (pin "1") (pinfunction "1_1") (pintype "passive"))
    )
    (net (code "56") (name "Net-(C49-Pad2)") (class "Default")
      (node (ref "C49") (pin "2") (pinfunction "2_2") (pintype "passive"))
      (node (ref "R48") (pin "2") (pinfunction "2_2") (pintype "passive"))
      (node (ref "R49") (pin "1") (pinfunction "1_1") (pintype "passive"))
    )
    (net (code "57") (name "Net-(C52-Pad2)") (class "Default")
      (node (ref "C52") (pin "2") (pinfunction "2_2") (pintype "passive"))
      (node (ref "R51") (pin "2") (pinfunction "2_2") (pintype "passive"))
      (node (ref "R52") (pin "1") (pinfunction "1_1") (pintype "passive"))
    )
    (net (code "58") (name "Net-(C54-Pad2)") (class "Default")
      (node (ref "C54") (pin "2") (pinfunction "2_2") (pintype "passive"))
      (node (ref "R53") (pin "2") (pinfunction "2_2") (pintype "passive"))
      (node (ref "R54") (pin "1") (pinfunction "1_1") (pintype "passive"))
    )
    (net (code "59") (name "Net-(C56-Pad2)") (class "Default")
      (node (ref "C56") (pin "2") (pinfunction "2_2") (pintype "passive"))
      (node (ref "R55") (pin "2") (pinfunction "2_2") (pintype "passive"))
      (node (ref "R56") (pin "1") (pinfunction "1_1") (pintype "passive"))
    )
    (net (code "60") (name "Net-(C58-Pad2)") (class "Default")
      (node (ref "C58") (pin "2") (pinfunction "2_2") (pintype "passive"))
      (node (ref "R57") (pin "2") (pinfunction "2_2") (pintype "passive"))
      (node (ref "R58") (pin "1") (pinfunction "1_1") (pintype "passive"))
    )
    (net (code "61") (name "Net-(R36-Pad1)") (class "Default")
      (node (ref "R36") (pin "1") (pinfunction "1_1") (pintype "passive"))
      (node (ref "R63") (pin "2") (pinfunction "2_2") (pintype "passive"))
    )
    (net (code "62") (name "Net-(U50-CH0)") (class "Default")
      (node (ref "C33") (pin "1") (pinfunction "1_1") (pintype "passive"))
      (node (ref "U50") (pin "1") (pinfunction "CH0_1") (pintype "passive"))
      (node (ref "U54") (pin "1") (pinfunction "OUT_1") (pintype "passive"))
      (node (ref "U54") (pin "2") (pinfunction "-_2") (pintype "passive"))
    )
    (net (code "63") (name "Net-(U50-CH1)") (class "Default")
      (node (ref "C35") (pin "1") (pinfunction "1_1") (pintype "passive"))
      (node (ref "U50") (pin "2") (pinfunction "CH1_2") (pintype "passive"))
      (node (ref "U54") (pin "6") (pinfunction "-_6") (pintype "passive"))
      (node (ref "U54") (pin "7") (pinfunction "OUT_7") (pintype "passive"))
    )
    (net (code "64") (name "Net-(U50-CH2)") (class "Default")
      (node (ref "C37") (pin "1") (pinfunction "1_1") (pintype "passive"))
      (node (ref "U50") (pin "3") (pinfunction "CH2_3") (pintype "passive"))
      (node (ref "U55") (pin "1") (pinfunction "OUT_1") (pintype "passive"))
      (node (ref "U55") (pin "2") (pinfunction "-_2") (pintype "passive"))
    )
    (net (code "65") (name "Net-(U50-CH3)") (class "Default")
      (node (ref "C39") (pin "1") (pinfunction "1_1") (pintype "passive"))
      (node (ref "U50") (pin "4") (pinfunction "CH3_4") (pintype "passive"))
      (node (ref "U55") (pin "6") (pinfunction "-_6") (pintype "passive"))
      (node (ref "U55") (pin "7") (pinfunction "OUT_7") (pintype "passive"))
    )
    (net (code "66") (name "Net-(U50-CH4)") (class "Default")
      (node (ref "C41") (pin "1") (pinfunction "1_1") (pintype "passive"))
      (node (ref "U50") (pin "5") (pinfunction "CH4_5") (pintype "passive"))
      (node (ref "U56") (pin "1") (pinfunction "OUT_1") (pintype "passive"))
      (node (ref "U56") (pin "2") (pinfunction "-_2") (pintype "passive"))
    )
    (net (code "67") (name "Net-(U50-CH5)") (class "Default")
      (node (ref "C43") (pin "1") (pinfunction "1_1") (pintype "passive"))
      (node (ref "U50") (pin "6") (pinfunction "CH5_6") (pintype "passive"))
      (node (ref "U56") (pin "6") (pinfunction "-_6") (pintype "passive"))
      (node (ref "U56") (pin "7") (pinfunction "OUT_7") (pintype "passive"))
    )
    (net (code "68") (name "Net-(U50-CH6)") (class "Default")
      (node (ref "C45") (pin "1") (pinfunction "1_1") (pintype "passive"))
      (node (ref "U50") (pin "7") (pinfunction "CH6_7") (pintype "passive"))
      (node (ref "U57") (pin "1") (pinfunction "OUT_1") (pintype "passive"))
      (node (ref "U57") (pin "2") (pinfunction "-_2") (pintype "passive"))
    )
    (net (code "69") (name "Net-(U50-CH7)") (class "Default")
      (node (ref "C47") (pin "1") (pinfunction "1_1") (pintype "passive"))
      (node (ref "U50") (pin "8") (pinfunction "CH7_8") (pintype "passive"))
      (node (ref "U62") (pin "6") (pinfunction "-_6") (pintype "passive"))
      (node (ref "U62") (pin "7") (pinfunction "OUT_7") (pintype "passive"))
    )
    (net (code "70") (name "Net-(U50-DOUT)") (class "Default")
      (node (ref "R35") (pin "1") (pinfunction "1_1") (pintype "passive"))
      (node (ref "U50") (pin "12") (pinfunction "DOUT_12") (pintype "passive"))
      (node (ref "U51") (pin "12") (pinfunction "DOUT_12") (pintype "passive"))
      (node (ref "U64") (pin "6") (pinfunction "D1_6") (pintype "passive"))
    )
    (net (code "71") (name "Net-(U51-CH0)") (class "Default")
      (node (ref "C49") (pin "1") (pinfunction "1_1") (pintype "passive"))
      (node (ref "U51") (pin "1") (pinfunction "CH0_1") (pintype "passive"))
      (node (ref "U63") (pin "6") (pinfunction "-_6") (pintype "passive"))
      (node (ref "U63") (pin "7") (pinfunction "OUT_7") (pintype "passive"))
    )
    (net (code "72") (name "Net-(U51-CH1)") (class "Default")
      (node (ref "C52") (pin "1") (pinfunction "1_1") (pintype "passive"))
      (node (ref "U51") (pin "2") (pinfunction "CH1_2") (pintype "passive"))
      (node (ref "U60") (pin "1") (pinfunction "OUT_1") (pintype "passive"))
      (node (ref "U60") (pin "2") (pinfunction "-_2") (pintype "passive"))
    )
    (net (code "73") (name "Net-(U51-CH2)") (class "Default")
      (node (ref "C54") (pin "1") (pinfunction "1_1") (pintype "passive"))
      (node (ref "U51") (pin "3") (pinfunction "CH2_3") (pintype "passive"))
      (node (ref "U60") (pin "6") (pinfunction "-_6") (pintype "passive"))
      (node (ref "U60") (pin "7") (pinfunction "OUT_7") (pintype "passive"))
    )
    (net (code "74") (name "Net-(U51-CH3)") (class "Default")
      (node (ref "C56") (pin "1") (pinfunction "1_1") (pintype "passive"))
      (node (ref "U51") (pin "4") (pinfunction "CH3_4") (pintype "passive"))
      (node (ref "U61") (pin "1") (pinfunction "OUT_1") (pintype "passive"))
      (node (ref "U61") (pin "2") (pinfunction "-_2") (pintype "passive"))
    )
    (net (code "75") (name "Net-(U51-CH4)") (class "Default")
      (node (ref "C58") (pin "1") (pinfunction "1_1") (pintype "passive"))
      (node (ref "U51") (pin "5") (pinfunction "CH4_5") (pintype "passive"))
      (node (ref "U61") (pin "6") (pinfunction "-_6") (pintype "passive"))
      (node (ref "U61") (pin "7") (pinfunction "OUT_7") (pintype "passive"))
    )
    (net (code "76") (name "Net-(U54A-+)") (class "Default")
      (node (ref "C34") (pin "2") (pinfunction "2_2") (pintype "passive"))
      (node (ref "R30") (pin "2") (pinfunction "2_2") (pintype "passive"))
      (node (ref "U54") (pin "3") (pinfunction "+_3") (pintype "passive"))
    )
    (net (code "77") (name "Net-(U54B-+)") (class "Default")
      (node (ref "C36") (pin "2") (pinfunction "2_2") (pintype "passive"))
      (node (ref "R32") (pin "2") (pinfunction "2_2") (pintype "passive"))
      (node (ref "U54") (pin "5") (pinfunction "+_5") (pintype "passive"))
    )
    (net (code "78") (name "Net-(U55A-+)") (class "Default")
      (node (ref "C38") (pin "2") (pinfunction "2_2") (pintype "passive"))
      (node (ref "R34") (pin "2") (pinfunction "2_2") (pintype "passive"))
      (node (ref "U55") (pin "3") (pinfunction "+_3") (pintype "passive"))
    )
    (net (code "79") (name "Net-(U55B-+)") (class "Default")
      (node (ref "C40") (pin "2") (pinfunction "2_2") (pintype "passive"))
      (node (ref "R38") (pin "2") (pinfunction "2_2") (pintype "passive"))
      (node (ref "U55") (pin "5") (pinfunction "+_5") (pintype "passive"))
    )
    (net (code "80") (name "Net-(U56A-+)") (class "Default")
      (node (ref "C42") (pin "2") (pinfunction "2_2") (pintype "passive"))
      (node (ref "R40") (pin "2") (pinfunction "2_2") (pintype "passive"))
      (node (ref "U56") (pin "3") (pinfunction "+_3") (pintype "passive"))
    )
    (net (code "81") (name "Net-(U56B-+)") (class "Default")
      (node (ref "C44") (pin "2") (pinfunction "2_2") (pintype "passive"))
      (node (ref "R42") (pin "2") (pinfunction "2_2") (pintype "passive"))
      (node (ref "U56") (pin "5") (pinfunction "+_5") (pintype "passive"))
    )
    (net (code "82") (name "Net-(U57A-+)") (class "Default")
      (node (ref "C46") (pin "2") (pinfunction "2_2") (pintype "passive"))
      (node (ref "R44") (pin "2") (pinfunction "2_2") (pintype "passive"))
      (node (ref "U57") (pin "3") (pinfunction "+_3") (pintype "passive"))
    )
    (net (code "83") (name "Net-(U60A-+)") (class "Default")
      (node (ref "C53") (pin "2") (pinfunction "2_2") (pintype "passive"))
      (node (ref "R52") (pin "2") (pinfunction "2_2") (pintype "passive"))
      (node (ref "U60") (pin "3") (pinfunction "+_3") (pintype "passive"))
    )
    (net (code "84") (name "Net-(U60B-+)") (class "Default")
      (node (ref "C55") (pin "2") (pinfunction "2_2") (pintype "passive"))
      (node (ref "R54") (pin "2") (pinfunction "2_2") (pintype "passive"))
      (node (ref "U60") (pin "5") (pinfunction "+_5") (pintype "passive"))
    )
    (net (code "85") (name "Net-(U61A-+)") (class "Default")
      (node (ref "C57") (pin "2") (pinfunction "2_2") (pintype "passive"))
      (node (ref "R56") (pin "2") (pinfunction "2_2") (pintype "passive"))
      (node (ref "U61") (pin "3") (pinfunction "+_3") (pintype "passive"))
    )
    (net (code "86") (name "Net-(U61B-+)") (class "Default")
      (node (ref "C59") (pin "2") (pinfunction "2_2") (pintype "passive"))
      (node (ref "R58") (pin "2") (pinfunction "2_2") (pintype "passive"))
      (node (ref "U61") (pin "5") (pinfunction "+_5") (pintype "passive"))
    )
    (net (code "87") (name "Net-(U62A--)") (class "Default")
      (node (ref "R45") (pin "1") (pinfunction "1_1") (pintype "passive"))
      (node (ref "U62") (pin "1") (pinfunction "OUT_1") (pintype "passive"))
      (node (ref "U62") (pin "2") (pinfunction "-_2") (pintype "passive"))
    )
    (net (code "88") (name "Net-(U62B-+)") (class "Default")
      (node (ref "C48") (pin "2") (pinfunction "2_2") (pintype "passive"))
      (node (ref "R46") (pin "2") (pinfunction "2_2") (pintype "passive"))
      (node (ref "U62") (pin "5") (pinfunction "+_5") (pintype "passive"))
    )
    (net (code "89") (name "Net-(U63A--)") (class "Default")
      (node (ref "R48") (pin "1") (pinfunction "1_1") (pintype "passive"))
      (node (ref "U63") (pin "1") (pinfunction "OUT_1") (pintype "passive"))
      (node (ref "U63") (pin "2") (pinfunction "-_2") (pintype "passive"))
    )
    (net (code "90") (name "Net-(U63B-+)") (class "Default")
      (node (ref "C50") (pin "2") (pinfunction "2_2") (pintype "passive"))
      (node (ref "R49") (pin "2") (pinfunction "2_2") (pintype "passive"))
      (node (ref "U63") (pin "5") (pinfunction "+_5") (pintype "passive"))
    )
    (net (code "91") (name "Net-(U64-DREF)") (class "Default")
      (node (ref "C64") (pin "1") (pinfunction "1_1") (pintype "passive"))
      (node (ref "R63") (pin "1") (pinfunction "1_1") (pintype "passive"))
      (node (ref "U64") (pin "7") (pinfunction "DREF_7") (pintype "passive"))
      (node (ref "U64") (pin "8") (pinfunction "GREF_8") (pintype "passive"))
    )
    (net (code "92") (name "unconnected-(U42-A7-Pad8)") (class "Default")
      (node (ref "U42") (pin "8") (pinfunction "A7_8") (pintype "passive"))
    )
    (net (code "93") (name "unconnected-(U42-A8-Pad9)") (class "Default")
      (node (ref "U42") (pin "9") (pinfunction "A8_9") (pintype "passive"))
    )
    (net (code "94") (name "unconnected-(U42-Y7-Pad12)") (class "Default")
      (node (ref "U42") (pin "12") (pinfunction "Y7_12") (pintype "passive"))
    )
    (net (code "95") (name "unconnected-(U42-Y8-Pad11)") (class "Default")
      (node (ref "U42") (pin "11") (pinfunction "Y8_11") (pintype "passive"))
    )
    (net (code "96") (name "unconnected-(U51-CH5-Pad6)") (class "Default")
      (node (ref "U51") (pin "6") (pinfunction "CH5_6") (pintype "passive"))
    )
    (net (code "97") (name "unconnected-(U51-CH6-Pad7)") (class "Default")
      (node (ref "U51") (pin "7") (pinfunction "CH6_7") (pintype "passive"))
    )
    (net (code "98") (name "unconnected-(U51-CH7-Pad8)") (class "Default")
      (node (ref "U51") (pin "8") (pinfunction "CH7_8") (pintype "passive"))
    )
    (net (code "99") (name "unconnected-(U52-DOUT-Pad19)") (class "Default")
      (node (ref "U52") (pin "19") (pinfunction "DOUT_19") (pintype "passive"))
    )
    (net (code "100") (name "unconnected-(U52-OUTH-Pad9)") (class "Default")
      (node (ref "U52") (pin "9") (pinfunction "OUTH_9") (pintype "passive"))
    )
    (net (code "101") (name "unconnected-(U58-DOUT-Pad19)") (class "Default")
      (node (ref "U58") (pin "19") (pinfunction "DOUT_19") (pintype "passive"))
    )
    (net (code "102") (name "unconnected-(U58-OUTE-Pad6)") (class "Default")
      (node (ref "U58") (pin "6") (pinfunction "OUTE_6") (pintype "passive"))
    )
    (net (code "103") (name "unconnected-(U58-OUTF-Pad7)") (class "Default")
      (node (ref "U58") (pin "7") (pinfunction "OUTF_7") (pintype "passive"))
    )
    (net (code "104") (name "unconnected-(U58-OUTG-Pad8)") (class "Default")
      (node (ref "U58") (pin "8") (pinfunction "OUTG_8") (pintype "passive"))
    )
    (net (code "105") (name "unconnected-(U58-OUTH-Pad9)") (class "Default")
      (node (ref "U58") (pin "9") (pinfunction "OUTH_9") (pintype "passive"))
    )
    (net (code "106") (name "unconnected-(U64-D2-Pad5)") (class "Default")
      (node (ref "U64") (pin "5") (pinfunction "D2_5") (pintype "passive"))
    )
    (net (code "107") (name "unconnected-(U64-S2-Pad4)") (class "Default")
      (node (ref "U64") (pin "4") (pinfunction "S2_4") (pintype "passive"))
    )
  )
)
